# 4WireTouch.net
KiCad netlist of a schematic drawn in EAGLE
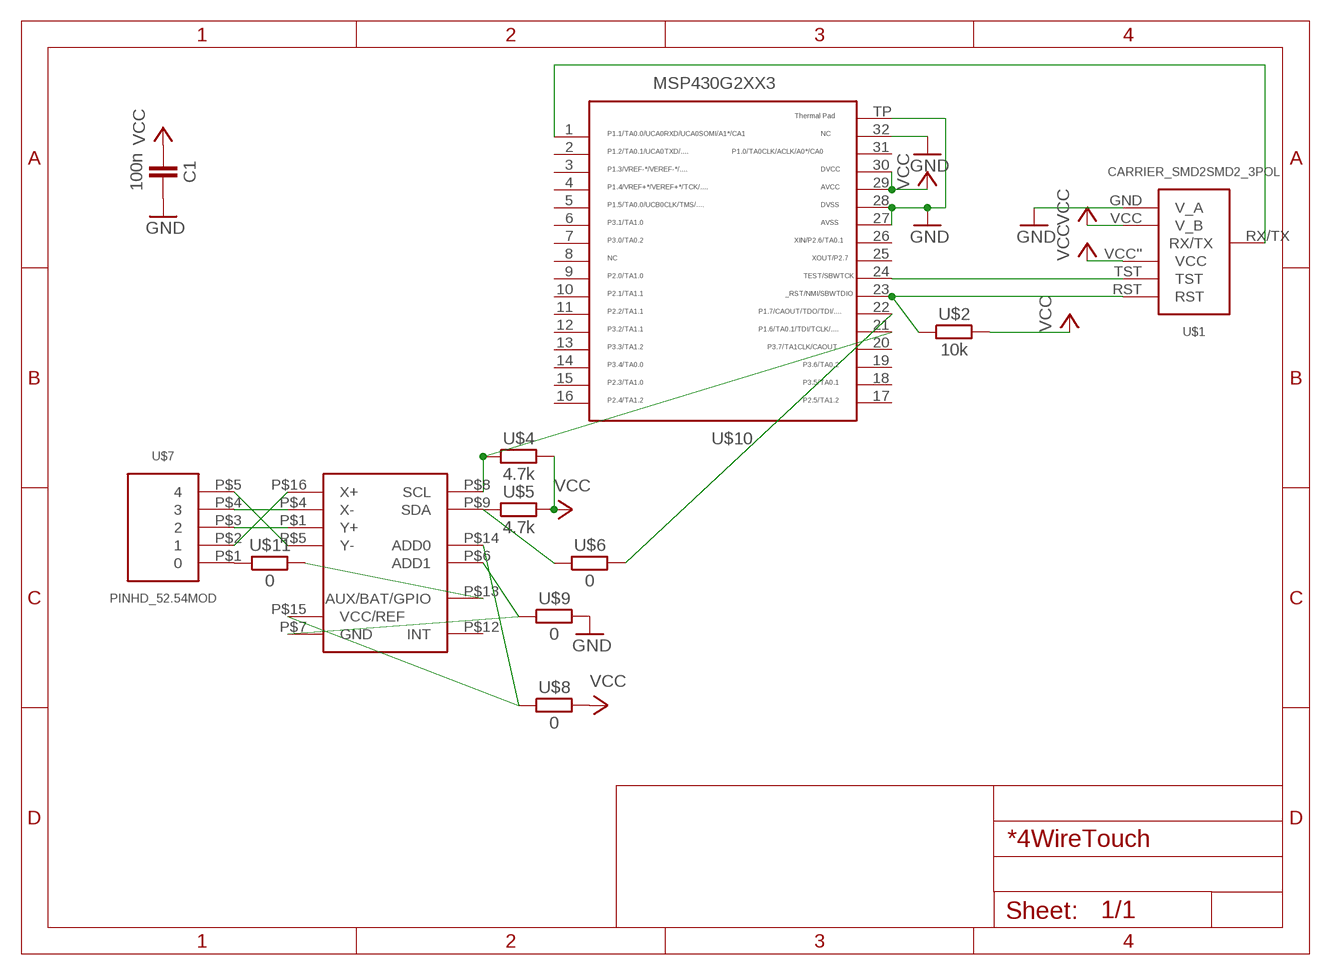
[diagram p0: schematic, sheet 1]

(export (version "E")
  (design (tool "Eeschema 10.0.6"))
  (components
    (comp (ref "C1")
      (value "100n")
      (footprint "eagle-import:603")
      (libsource (lib "eagle-import") (part "CAPACITOR"))
    )
    (comp (ref "U$1")
      (value "CARRIER_SMD2SMD2_3POL")
      (footprint "eagle-import:CARRIER_SMD2_3POL")
      (libsource (lib "eagle-import") (part "CARRIER_SMD2SMD2_3POL"))
    )
    (comp (ref "U$2")
      (value "10k")
      (footprint "eagle-import:603")
      (libsource (lib "eagle-import") (part "RESISTOR0603"))
    )
    (comp (ref "U$3")
      (value "AD7879")
      (footprint "eagle-import:LFCSP")
      (libsource (lib "eagle-import") (part "AD7879"))
    )
    (comp (ref "U$4")
      (value "4.7k")
      (footprint "eagle-import:603")
      (libsource (lib "eagle-import") (part "RESISTOR0603"))
    )
    (comp (ref "U$5")
      (value "4.7k")
      (footprint "eagle-import:603")
      (libsource (lib "eagle-import") (part "RESISTOR0603"))
    )
    (comp (ref "U$6")
      (value "0")
      (footprint "eagle-import:603")
      (libsource (lib "eagle-import") (part "RESISTOR0603"))
    )
    (comp (ref "U$7")
      (value "PINHD_52.54MOD")
      (footprint "eagle-import:PINHD_5_MOD")
      (libsource (lib "eagle-import") (part "PINHD_52.54MOD"))
    )
    (comp (ref "U$8")
      (value "0")
      (footprint "eagle-import:603")
      (libsource (lib "eagle-import") (part "RESISTOR0603"))
    )
    (comp (ref "U$9")
      (value "0")
      (footprint "eagle-import:603")
      (libsource (lib "eagle-import") (part "RESISTOR0603"))
    )
    (comp (ref "U$10")
      (value "MSP430G2553")
      (footprint "eagle-import:QFN32")
      (libsource (lib "eagle-import") (part "MSP430G2553"))
    )
    (comp (ref "U$11")
      (value "0")
      (footprint "eagle-import:603")
      (libsource (lib "eagle-import") (part "RESISTOR0603"))
    )
  )
  (nets
    (net (code "1") (name "GND") (class "Default")
      (node (ref "C1") (pin "2") (pinfunction "2_2") (pintype "passive"))
      (node (ref "U$1") (pin "GND") (pinfunction "V_A_GND") (pintype "bidirectional"))
      (node (ref "U$10") (pin "27") (pinfunction "27_27") (pintype "bidirectional"))
      (node (ref "U$10") (pin "28") (pinfunction "28_28") (pintype "bidirectional"))
      (node (ref "U$10") (pin "32") (pinfunction "32_32") (pintype "bidirectional"))
      (node (ref "U$10") (pin "TP") (pinfunction "TP_TP") (pintype "bidirectional"))
      (node (ref "U$9") (pin "2") (pinfunction "2_2") (pintype "passive"))
    )
    (net (code "2") (name "Net-(U$1-PadRST)") (class "Default")
      (node (ref "U$1") (pin "RST") (pinfunction "RST_RST") (pintype "bidirectional"))
      (node (ref "U$10") (pin "23") (pinfunction "23_23") (pintype "bidirectional"))
      (node (ref "U$2") (pin "1") (pinfunction "1_1") (pintype "passive"))
    )
    (net (code "3") (name "Net-(U$1-PadRX{slash}TX)") (class "Default")
      (node (ref "U$1") (pin "RX/TX") (pinfunction "RX/TX_RX/TX") (pintype "bidirectional"))
      (node (ref "U$10") (pin "1") (pinfunction "1_1") (pintype "bidirectional"))
    )
    (net (code "4") (name "Net-(U$1-PadTST)") (class "Default")
      (node (ref "U$1") (pin "TST") (pinfunction "TST_TST") (pintype "bidirectional"))
      (node (ref "U$10") (pin "24") (pinfunction "24_24") (pintype "bidirectional"))
    )
    (net (code "5") (name "Net-(U$3-ADD0)") (class "Default")
      (node (ref "U$3") (pin "P$14") (pinfunction "ADD0_P$14") (pintype "bidirectional"))
      (node (ref "U$3") (pin "P$15") (pinfunction "VCC/REF_P$15") (pintype "bidirectional"))
      (node (ref "U$8") (pin "1") (pinfunction "1_1") (pintype "passive"))
    )
    (net (code "6") (name "Net-(U$3-ADD1)") (class "Default")
      (node (ref "U$3") (pin "P$6") (pinfunction "ADD1_P$6") (pintype "bidirectional"))
      (node (ref "U$3") (pin "P$7") (pinfunction "GND_P$7") (pintype "bidirectional"))
      (node (ref "U$9") (pin "1") (pinfunction "1_1") (pintype "passive"))
    )
    (net (code "7") (name "Net-(U$3-AUX{slash}BAT{slash}GPIO)") (class "Default")
      (node (ref "U$11") (pin "2") (pinfunction "2_2") (pintype "passive"))
      (node (ref "U$3") (pin "P$13") (pinfunction "AUX/BAT/GPIO_P$13") (pintype "bidirectional"))
    )
    (net (code "8") (name "Net-(U$3-SCL)") (class "Default")
      (node (ref "U$10") (pin "21") (pinfunction "21_21") (pintype "bidirectional"))
      (node (ref "U$3") (pin "P$8") (pinfunction "SCL_P$8") (pintype "bidirectional"))
      (node (ref "U$4") (pin "1") (pinfunction "1_1") (pintype "passive"))
    )
    (net (code "9") (name "Net-(U$3-SDA)") (class "Default")
      (node (ref "U$3") (pin "P$9") (pinfunction "SDA_P$9") (pintype "bidirectional"))
      (node (ref "U$5") (pin "1") (pinfunction "1_1") (pintype "passive"))
      (node (ref "U$6") (pin "1") (pinfunction "1_1") (pintype "passive"))
    )
    (net (code "10") (name "Net-(U$3-X+)") (class "Default")
      (node (ref "U$3") (pin "P$16") (pinfunction "X+_P$16") (pintype "bidirectional"))
      (node (ref "U$7") (pin "P$2") (pinfunction "1_P$2") (pintype "bidirectional"))
    )
    (net (code "11") (name "Net-(U$3-X-)") (class "Default")
      (node (ref "U$3") (pin "P$4") (pinfunction "X-_P$4") (pintype "bidirectional"))
      (node (ref "U$7") (pin "P$4") (pinfunction "3_P$4") (pintype "bidirectional"))
    )
    (net (code "12") (name "Net-(U$3-Y+)") (class "Default")
      (node (ref "U$3") (pin "P$1") (pinfunction "Y+_P$1") (pintype "bidirectional"))
      (node (ref "U$7") (pin "P$3") (pinfunction "2_P$3") (pintype "bidirectional"))
    )
    (net (code "13") (name "Net-(U$3-Y-)") (class "Default")
      (node (ref "U$3") (pin "P$5") (pinfunction "Y-_P$5") (pintype "bidirectional"))
      (node (ref "U$7") (pin "P$5") (pinfunction "4_P$5") (pintype "bidirectional"))
    )
    (net (code "14") (name "Net-(U$7-0)") (class "Default")
      (node (ref "U$11") (pin "1") (pinfunction "1_1") (pintype "passive"))
      (node (ref "U$7") (pin "P$1") (pinfunction "0_P$1") (pintype "bidirectional"))
    )
    (net (code "15") (name "Net-(U$10-Pad22)") (class "Default")
      (node (ref "U$10") (pin "22") (pinfunction "22_22") (pintype "bidirectional"))
      (node (ref "U$6") (pin "2") (pinfunction "2_2") (pintype "passive"))
    )
    (net (code "16") (name "VCC") (class "Default")
      (node (ref "C1") (pin "1") (pinfunction "1_1") (pintype "passive"))
      (node (ref "U$1") (pin "VCC") (pinfunction "V_B_VCC") (pintype "bidirectional"))
      (node (ref "U$1") (pin "VCC''") (pinfunction "VCC_VCC''") (pintype "bidirectional"))
      (node (ref "U$10") (pin "29") (pinfunction "29_29") (pintype "bidirectional"))
      (node (ref "U$10") (pin "30") (pinfunction "30_30") (pintype "bidirectional"))
      (node (ref "U$2") (pin "2") (pinfunction "2_2") (pintype "passive"))
      (node (ref "U$4") (pin "2") (pinfunction "2_2") (pintype "passive"))
      (node (ref "U$5") (pin "2") (pinfunction "2_2") (pintype "passive"))
      (node (ref "U$8") (pin "2") (pinfunction "2_2") (pintype "passive"))
    )
    (net (code "17") (name "unconnected-(U$3-INT-PadP$12)") (class "Default")
      (node (ref "U$3") (pin "P$12") (pinfunction "INT_P$12") (pintype "bidirectional"))
    )
    (net (code "18") (name "unconnected-(U$10-Pad2)") (class "Default")
      (node (ref "U$10") (pin "2") (pinfunction "2_2") (pintype "bidirectional"))
    )
    (net (code "19") (name "unconnected-(U$10-Pad3)") (class "Default")
      (node (ref "U$10") (pin "3") (pinfunction "3_3") (pintype "bidirectional"))
    )
    (net (code "20") (name "unconnected-(U$10-Pad4)") (class "Default")
      (node (ref "U$10") (pin "4") (pinfunction "4_4") (pintype "bidirectional"))
    )
    (net (code "21") (name "unconnected-(U$10-Pad5)") (class "Default")
      (node (ref "U$10") (pin "5") (pinfunction "5_5") (pintype "bidirectional"))
    )
    (net (code "22") (name "unconnected-(U$10-Pad6)") (class "Default")
      (node (ref "U$10") (pin "6") (pinfunction "6_6") (pintype "bidirectional"))
    )
    (net (code "23") (name "unconnected-(U$10-Pad7)") (class "Default")
      (node (ref "U$10") (pin "7") (pinfunction "7_7") (pintype "bidirectional"))
    )
    (net (code "24") (name "unconnected-(U$10-Pad8)") (class "Default")
      (node (ref "U$10") (pin "8") (pinfunction "8_8") (pintype "bidirectional"))
    )
    (net (code "25") (name "unconnected-(U$10-Pad9)") (class "Default")
      (node (ref "U$10") (pin "9") (pinfunction "9_9") (pintype "bidirectional"))
    )
    (net (code "26") (name "unconnected-(U$10-Pad10)") (class "Default")
      (node (ref "U$10") (pin "10") (pinfunction "10_10") (pintype "bidirectional"))
    )
    (net (code "27") (name "unconnected-(U$10-Pad11)") (class "Default")
      (node (ref "U$10") (pin "11") (pinfunction "11_11") (pintype "bidirectional"))
    )
    (net (code "28") (name "unconnected-(U$10-Pad12)") (class "Default")
      (node (ref "U$10") (pin "12") (pinfunction "12_12") (pintype "bidirectional"))
    )
    (net (code "29") (name "unconnected-(U$10-Pad13)") (class "Default")
      (node (ref "U$10") (pin "13") (pinfunction "13_13") (pintype "bidirectional"))
    )
    (net (code "30") (name "unconnected-(U$10-Pad14)") (class "Default")
      (node (ref "U$10") (pin "14") (pinfunction "14_14") (pintype "bidirectional"))
    )
    (net (code "31") (name "unconnected-(U$10-Pad15)") (class "Default")
      (node (ref "U$10") (pin "15") (pinfunction "15_15") (pintype "bidirectional"))
    )
    (net (code "32") (name "unconnected-(U$10-Pad16)") (class "Default")
      (node (ref "U$10") (pin "16") (pinfunction "16_16") (pintype "bidirectional"))
    )
    (net (code "33") (name "unconnected-(U$10-Pad17)") (class "Default")
      (node (ref "U$10") (pin "17") (pinfunction "17_17") (pintype "bidirectional"))
    )
    (net (code "34") (name "unconnected-(U$10-Pad18)") (class "Default")
      (node (ref "U$10") (pin "18") (pinfunction "18_18") (pintype "bidirectional"))
    )
    (net (code "35") (name "unconnected-(U$10-Pad19)") (class "Default")
      (node (ref "U$10") (pin "19") (pinfunction "19_19") (pintype "bidirectional"))
    )
    (net (code "36") (name "unconnected-(U$10-Pad20)") (class "Default")
      (node (ref "U$10") (pin "20") (pinfunction "20_20") (pintype "bidirectional"))
    )
    (net (code "37") (name "unconnected-(U$10-Pad25)") (class "Default")
      (node (ref "U$10") (pin "25") (pinfunction "25_25") (pintype "bidirectional"))
    )
    (net (code "38") (name "unconnected-(U$10-Pad26)") (class "Default")
      (node (ref "U$10") (pin "26") (pinfunction "26_26") (pintype "bidirectional"))
    )
    (net (code "39") (name "unconnected-(U$10-Pad31)") (class "Default")
      (node (ref "U$10") (pin "31") (pinfunction "31_31") (pintype "bidirectional"))
    )
  )
)
